# LatarSnapProbes.net
KiCad netlist of a schematic drawn in EAGLE
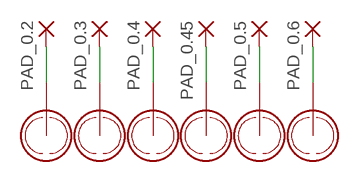
[diagram p0: schematic, sheet 1]

(export (version "E")
  (design (tool "Eeschema 10.0.6"))
  (components
    (comp (ref "P1")
      (value "PROBE_0.2_IN")
      (footprint "eagle-import:PROBE_0.2_IN")
      (libsource (lib "eagle-import") (part "PROBE_0.2_IN"))
    )
    (comp (ref "PAD_0.2")
      (value "SMD5")
      (footprint "eagle-import:SMD2,54-5,08")
      (libsource (lib "eagle-import") (part "SMD5"))
    )
    (comp (ref "PAD_0.3")
      (value "SMD5")
      (footprint "eagle-import:SMD2,54-5,08")
      (libsource (lib "eagle-import") (part "SMD5"))
    )
    (comp (ref "PAD_0.4")
      (value "SMD5")
      (footprint "eagle-import:SMD2,54-5,08")
      (libsource (lib "eagle-import") (part "SMD5"))
    )
    (comp (ref "PAD_0.5")
      (value "SMD5")
      (footprint "eagle-import:SMD2,54-5,08")
      (libsource (lib "eagle-import") (part "SMD5"))
    )
    (comp (ref "PAD_0.6")
      (value "SMD5")
      (footprint "eagle-import:SMD2,54-5,08")
      (libsource (lib "eagle-import") (part "SMD5"))
    )
    (comp (ref "PAD_0.45")
      (value "SMD5")
      (footprint "eagle-import:SMD2,54-5,08")
      (libsource (lib "eagle-import") (part "SMD5"))
    )
    (comp (ref "U$1")
      (value "PROBE_0.4_IN")
      (footprint "eagle-import:PROBE_0.4_IN")
      (libsource (lib "eagle-import") (part "PROBE_0.4_IN"))
    )
    (comp (ref "U$3")
      (value "PROBE_0.3_IN")
      (footprint "eagle-import:PROBE_0.3_IN")
      (libsource (lib "eagle-import") (part "PROBE_0.3_IN"))
    )
    (comp (ref "U$4")
      (value "PROBE_0.45_IN")
      (footprint "eagle-import:PROBE_0.45_IN")
      (libsource (lib "eagle-import") (part "PROBE_0.45_IN"))
    )
    (comp (ref "U$5")
      (value "PROBE_0.5_IN")
      (footprint "eagle-import:PROBE_0.5_IN")
      (libsource (lib "eagle-import") (part "PROBE_0.5_IN"))
    )
    (comp (ref "U$6")
      (value "PROBE_0.6_IN")
      (footprint "eagle-import:PROBE_0.6_IN")
      (libsource (lib "eagle-import") (part "PROBE_0.6_IN"))
    )
  )
  (nets
    (net (code "1") (name "Net-(PAD_0.2-P)") (class "Default")
      (node (ref "P1") (pin "P1") (pinfunction "P$1_P1") (pintype "bidirectional"))
      (node (ref "P1") (pin "P2") (pinfunction "P$1_P2") (pintype "bidirectional"))
      (node (ref "PAD_0.2") (pin "1") (pinfunction "P_1") (pintype "passive"))
    )
    (net (code "2") (name "Net-(PAD_0.3-P)") (class "Default")
      (node (ref "PAD_0.3") (pin "1") (pinfunction "P_1") (pintype "passive"))
      (node (ref "U$3") (pin "P1") (pinfunction "P$1_P1") (pintype "bidirectional"))
      (node (ref "U$3") (pin "P2") (pinfunction "P$1_P2") (pintype "bidirectional"))
    )
    (net (code "3") (name "Net-(PAD_0.4-P)") (class "Default")
      (node (ref "PAD_0.4") (pin "1") (pinfunction "P_1") (pintype "passive"))
      (node (ref "U$1") (pin "P1") (pinfunction "P$1_P1") (pintype "bidirectional"))
      (node (ref "U$1") (pin "P2") (pinfunction "P$1_P2") (pintype "bidirectional"))
    )
    (net (code "4") (name "Net-(PAD_0.5-P)") (class "Default")
      (node (ref "PAD_0.5") (pin "1") (pinfunction "P_1") (pintype "passive"))
      (node (ref "U$5") (pin "P1") (pinfunction "P$1_P1") (pintype "bidirectional"))
      (node (ref "U$5") (pin "P2") (pinfunction "P$1_P2") (pintype "bidirectional"))
    )
    (net (code "5") (name "Net-(PAD_0.6-P)") (class "Default")
      (node (ref "PAD_0.6") (pin "1") (pinfunction "P_1") (pintype "passive"))
      (node (ref "U$6") (pin "P1") (pinfunction "P$1_P1") (pintype "bidirectional"))
      (node (ref "U$6") (pin "P2") (pinfunction "P$1_P2") (pintype "bidirectional"))
    )
    (net (code "6") (name "Net-(PAD_0.45-P)") (class "Default")
      (node (ref "PAD_0.45") (pin "1") (pinfunction "P_1") (pintype "passive"))
      (node (ref "U$4") (pin "P1") (pinfunction "P$1_P1") (pintype "bidirectional"))
      (node (ref "U$4") (pin "P2") (pinfunction "P$1_P2") (pintype "bidirectional"))
    )
  )
)
